# v1_0.net
KiCad netlist of a schematic drawn in Altium Designer
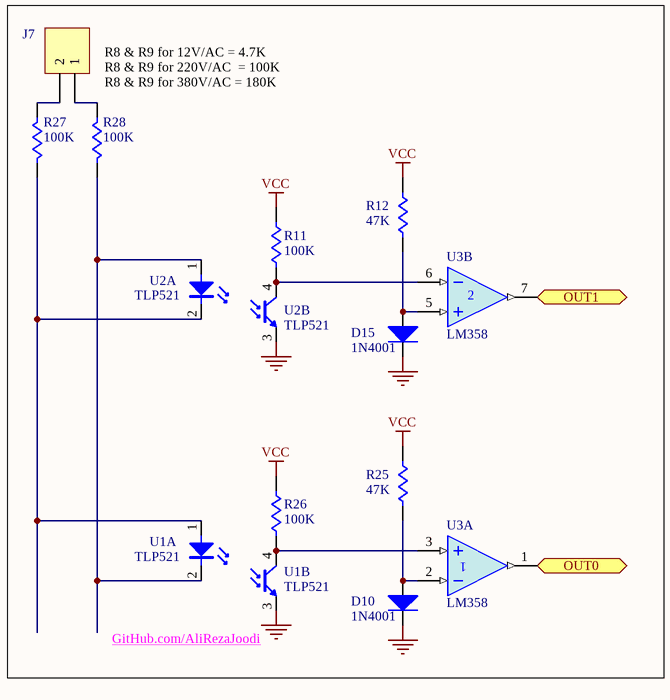
[diagram p0: v1.0.SchDoc]

(export (version "E")
  (design (tool "Eeschema 10.0.6"))
  (components
    (comp (ref "D10")
      (value "1N4001")
      (footprint "DIODE-0.4")
      (description "Default Diode")
      (fields (field (name "MANUFACTURER") "Generic Components") (field (name "PUBLISHER") "Altium Limited"))
      (libsource (lib "Miscellaneous Devices") (part "Diode"))
    )
    (comp (ref "D15")
      (value "1N4001")
      (footprint "DIODE-0.4")
      (description "Default Diode")
      (fields (field (name "MANUFACTURER") "Generic Components") (field (name "PUBLISHER") "Altium Limited"))
      (libsource (lib "Miscellaneous Devices") (part "Diode"))
    )
    (comp (ref "J7")
      (value "Header 2")
      (footprint "Fonics_2PIN_1")
      (description "Header, 2-Pin")
      (fields (field (name "PUBLISHER") "Altium Limited"))
      (libsource (lib "Miscellaneous Connectors") (part "Header 2"))
    )
    (comp (ref "R11")
      (value "100K")
      (footprint "AXIAL-0.4")
      (description "Resistor")
      (fields
        (field (name "MANUFACTURER") "Generic Components")
        (field (name "Comment") "Res1")
        (field (name "PUBLISHER") "Altium Limited")
      )
      (libsource (lib "Miscellaneous Devices") (part "Res1"))
    )
    (comp (ref "R12")
      (value "47K")
      (footprint "AXIAL-0.4")
      (description "Resistor")
      (fields
        (field (name "MANUFACTURER") "Generic Components")
        (field (name "Comment") "Res1")
        (field (name "PUBLISHER") "Altium Limited")
      )
      (libsource (lib "Miscellaneous Devices") (part "Res1"))
    )
    (comp (ref "R25")
      (value "47K")
      (footprint "AXIAL-0.4")
      (description "Resistor")
      (fields
        (field (name "MANUFACTURER") "Generic Components")
        (field (name "Comment") "Res1")
        (field (name "PUBLISHER") "Altium Limited")
      )
      (libsource (lib "Miscellaneous Devices") (part "Res1"))
    )
    (comp (ref "R26")
      (value "100K")
      (footprint "AXIAL-0.4")
      (description "Resistor")
      (fields
        (field (name "MANUFACTURER") "Generic Components")
        (field (name "Comment") "Res1")
        (field (name "PUBLISHER") "Altium Limited")
      )
      (libsource (lib "Miscellaneous Devices") (part "Res1"))
    )
    (comp (ref "R27")
      (value "100K")
      (footprint "AXIAL-0.4")
      (description "Resistor")
      (fields
        (field (name "MANUFACTURER") "Generic Components")
        (field (name "Comment") "Res1")
        (field (name "PUBLISHER") "Altium Limited")
      )
      (libsource (lib "Miscellaneous Devices") (part "Res1"))
    )
    (comp (ref "R28")
      (value "100K")
      (footprint "AXIAL-0.4")
      (description "Resistor")
      (fields
        (field (name "MANUFACTURER") "Generic Components")
        (field (name "Comment") "Res1")
        (field (name "PUBLISHER") "Altium Limited")
      )
      (libsource (lib "Miscellaneous Devices") (part "Res1"))
    )
    (comp (ref "U1")
      (value "TLP521")
      (footprint "DIP-4")
      (fields (field (name "Comment") "Optoisolator") (field (name "PUBLISHER") "Altium Limited"))
      (libsource (lib "my Libraries") (part "Optoisolator"))
    )
    (comp (ref "U2")
      (value "TLP521")
      (footprint "DIP-4")
      (fields (field (name "Comment") "Optoisolator") (field (name "PUBLISHER") "Altium Limited"))
      (libsource (lib "my Libraries") (part "Optoisolator"))
    )
    (comp (ref "U3")
      (value "LM358")
      (footprint "DIP_8")
      (description "Dual Low-Power Operational Amplifier")
      (fields (field (name "PUBLISHER") "Altium Limited"))
      (libsource (lib "") (part "LM358_1"))
    )
  )
  (nets
    (net (code "1") (name "/OUT0") (class "Default")
      (node (ref "U3") (pin "1") (pinfunction "OUT_1") (pintype "output"))
    )
    (net (code "2") (name "/OUT1") (class "Default")
      (node (ref "U3") (pin "7") (pinfunction "OUT_7") (pintype "output"))
    )
    (net (code "3") (name "GND") (class "Default")
      (node (ref "D10") (pin "2") (pinfunction "K_2") (pintype "passive"))
      (node (ref "D15") (pin "2") (pinfunction "K_2") (pintype "passive"))
      (node (ref "U1") (pin "3") (pinfunction "E_3") (pintype "passive"))
      (node (ref "U2") (pin "3") (pinfunction "E_3") (pintype "passive"))
    )
    (net (code "4") (name "Net-(D10-A)") (class "Default")
      (node (ref "D10") (pin "1") (pinfunction "A_1") (pintype "passive"))
      (node (ref "R25") (pin "2") (pinfunction "2_2") (pintype "passive"))
      (node (ref "U3") (pin "2") (pinfunction "IN-_2") (pintype "input"))
    )
    (net (code "5") (name "Net-(D15-A)") (class "Default")
      (node (ref "D15") (pin "1") (pinfunction "A_1") (pintype "passive"))
      (node (ref "R12") (pin "2") (pinfunction "2_2") (pintype "passive"))
      (node (ref "U3") (pin "5") (pinfunction "IN+_5") (pintype "input"))
    )
    (net (code "6") (name "Net-(J7-Pad1)") (class "Default")
      (node (ref "J7") (pin "1") (pinfunction "1_1") (pintype "passive"))
      (node (ref "R28") (pin "1") (pinfunction "1_1") (pintype "passive"))
    )
    (net (code "7") (name "Net-(J7-Pad2)") (class "Default")
      (node (ref "J7") (pin "2") (pinfunction "2_2") (pintype "passive"))
      (node (ref "R27") (pin "1") (pinfunction "1_1") (pintype "passive"))
    )
    (net (code "8") (name "Net-(U1A-A)") (class "Default")
      (node (ref "R27") (pin "2") (pinfunction "2_2") (pintype "passive"))
      (node (ref "U1") (pin "1") (pinfunction "A_1") (pintype "power_in"))
      (node (ref "U2") (pin "2") (pinfunction "K_2") (pintype "power_in"))
    )
    (net (code "9") (name "Net-(U1A-K)") (class "Default")
      (node (ref "R28") (pin "2") (pinfunction "2_2") (pintype "passive"))
      (node (ref "U1") (pin "2") (pinfunction "K_2") (pintype "power_in"))
      (node (ref "U2") (pin "1") (pinfunction "A_1") (pintype "power_in"))
    )
    (net (code "10") (name "Net-(U1B-C)") (class "Default")
      (node (ref "R26") (pin "2") (pinfunction "2_2") (pintype "passive"))
      (node (ref "U1") (pin "4") (pinfunction "C_4") (pintype "passive"))
      (node (ref "U3") (pin "3") (pinfunction "IN+_3") (pintype "input"))
    )
    (net (code "11") (name "Net-(U2B-C)") (class "Default")
      (node (ref "R11") (pin "2") (pinfunction "2_2") (pintype "passive"))
      (node (ref "U2") (pin "4") (pinfunction "C_4") (pintype "passive"))
      (node (ref "U3") (pin "6") (pinfunction "IN-_6") (pintype "input"))
    )
    (net (code "12") (name "VCC") (class "Default")
      (node (ref "R11") (pin "1") (pinfunction "1_1") (pintype "passive"))
      (node (ref "R12") (pin "1") (pinfunction "1_1") (pintype "passive"))
      (node (ref "R25") (pin "1") (pinfunction "1_1") (pintype "passive"))
      (node (ref "R26") (pin "1") (pinfunction "1_1") (pintype "passive"))
    )
  )
)
